# devices.net
KiCad netlist of a schematic drawn in Altium Designer
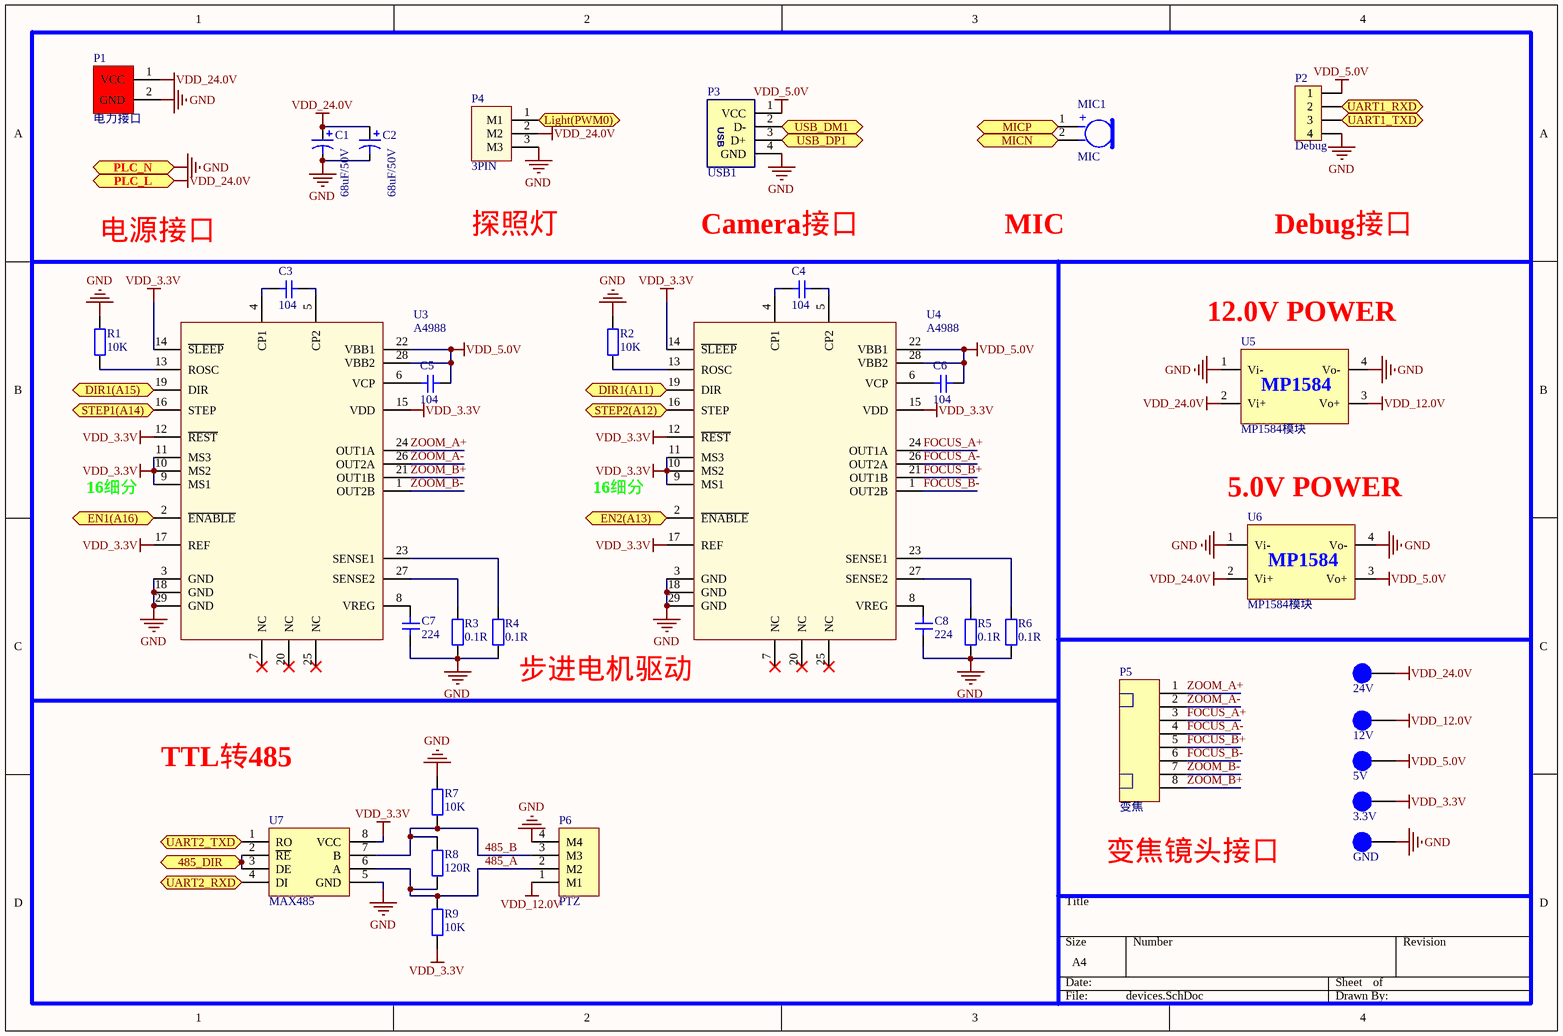
[diagram p0: devices.SchDoc]

(export (version "E")
  (design (tool "Eeschema 10.0.6"))
  (components
    (comp (ref "C1")
      (value "68uF/50V")
      (footprint "RB.1.2")
      (description "直插极性电容")
      (libsource (lib "集大电协1.5") (part "Cap3"))
    )
    (comp (ref "C2")
      (value "68uF/50V")
      (footprint "RB.1.2")
      (description "直插极性电容")
      (libsource (lib "集大电协1.5") (part "Cap3"))
    )
    (comp (ref "C3")
      (value "104")
      (footprint "0603C")
      (description "无极贴片电容")
      (libsource (lib "集大电协1.5") (part "Cap1"))
    )
    (comp (ref "C4")
      (value "104")
      (footprint "0603C")
      (description "无极贴片电容")
      (libsource (lib "集大电协1.5") (part "Cap1"))
    )
    (comp (ref "C5")
      (value "104")
      (footprint "0603C")
      (description "无极贴片电容")
      (libsource (lib "集大电协1.5") (part "Cap1"))
    )
    (comp (ref "C6")
      (value "104")
      (footprint "0603C")
      (description "无极贴片电容")
      (libsource (lib "集大电协1.5") (part "Cap1"))
    )
    (comp (ref "C7")
      (value "224")
      (footprint "0603C")
      (description "无极贴片电容")
      (libsource (lib "集大电协1.5") (part "Cap1"))
    )
    (comp (ref "C8")
      (value "224")
      (footprint "0603C")
      (description "无极贴片电容")
      (libsource (lib "集大电协1.5") (part "Cap1"))
    )
    (comp (ref "MIC1") (value "MIC") (footprint "MIC") (libsource (lib "集大电协1.5") (part "MIC")))
    (comp (ref "P1") (value "电力接口") (footprint "PH2.0WS-2P") (libsource (lib "集大电协1.5") (part "电源端子")))
    (comp (ref "P2")
      (value "Debug")
      (footprint "MX1.25WS-4PIN")
      (description "排针")
      (libsource (lib "集大电协1.5") (part "Header 4"))
    )
    (comp (ref "P3") (value "USB1") (footprint "PH2.0WS-4P") (libsource (lib "集大电协1.5") (part "USB")))
    (comp (ref "P4") (value "3PIN") (footprint "PH2.0WS-3P") (libsource (lib "集大电协1.5") (part "接线端子-3PIN")))
    (comp (ref "P5") (value "变焦") (footprint "MX1.25WS-8P") (libsource (lib "集大电协1.5") (part "接线端子-8PIN")))
    (comp (ref "P6")
      (value "PTZ")
      (footprint "PH2.0WS-4P")
      (description "4PIN")
      (libsource (lib "集大电协1.5") (part "接线端子-4PIN"))
    )
    (comp (ref "R1")
      (value "10K")
      (footprint "0603R")
      (description "电阻")
      (libsource (lib "集大电协1.5") (part "Res"))
    )
    (comp (ref "R2")
      (value "10K")
      (footprint "0603R")
      (description "电阻")
      (libsource (lib "集大电协1.5") (part "Res"))
    )
    (comp (ref "R3")
      (value "0.1R")
      (footprint "0805R")
      (description "电阻")
      (libsource (lib "集大电协1.5") (part "Res"))
    )
    (comp (ref "R4")
      (value "0.1R")
      (footprint "0805R")
      (description "电阻")
      (libsource (lib "集大电协1.5") (part "Res"))
    )
    (comp (ref "R5")
      (value "0.1R")
      (footprint "0805R")
      (description "电阻")
      (libsource (lib "集大电协1.5") (part "Res"))
    )
    (comp (ref "R6")
      (value "0.1R")
      (footprint "0805R")
      (description "电阻")
      (libsource (lib "集大电协1.5") (part "Res"))
    )
    (comp (ref "R7")
      (value "10K")
      (footprint "0603R")
      (description "电阻")
      (libsource (lib "集大电协1.5") (part "Res"))
    )
    (comp (ref "R8")
      (value "120R")
      (footprint "0603R")
      (description "电阻")
      (libsource (lib "集大电协1.5") (part "Res"))
    )
    (comp (ref "R9")
      (value "10K")
      (footprint "0603R")
      (description "电阻")
      (libsource (lib "集大电协1.5") (part "Res"))
    )
    (comp (ref "T1")
      (value "24V")
      (footprint "PIN 1(贴片)")
      (description "测试点")
      (libsource (lib "集大电协1.2") (part "测试点"))
    )
    (comp (ref "T2")
      (value "12V")
      (footprint "PIN 1(贴片)")
      (description "测试点")
      (libsource (lib "集大电协1.2") (part "测试点"))
    )
    (comp (ref "T3")
      (value "5V")
      (footprint "PIN 1(贴片)")
      (description "测试点")
      (libsource (lib "集大电协1.2") (part "测试点"))
    )
    (comp (ref "T4")
      (value "3.3V")
      (footprint "PIN 1(贴片)")
      (description "测试点")
      (libsource (lib "集大电协1.2") (part "测试点"))
    )
    (comp (ref "T5")
      (value "GND")
      (footprint "PIN 1(贴片)")
      (description "测试点")
      (libsource (lib "集大电协1.2") (part "测试点"))
    )
    (comp (ref "U3") (value "A4988") (footprint "QFN-28") (libsource (lib "集大电协1.5") (part "A4988")))
    (comp (ref "U4") (value "A4988") (footprint "QFN-28") (libsource (lib "集大电协1.5") (part "A4988")))
    (comp (ref "U5")
      (value "MP1584模块")
      (footprint "MP1584电源模块")
      (libsource (lib "集大电协1.5") (part "MP1584电源模块"))
    )
    (comp (ref "U6")
      (value "MP1584模块")
      (footprint "MP1584电源模块")
      (libsource (lib "集大电协1.5") (part "MP1584电源模块"))
    )
    (comp (ref "U7") (value "MAX485") (footprint "SOP-8") (libsource (lib "集大电协1.5") (part "MAX485")))
  )
  (nets
    (net (code "1") (name "/485_A") (class "Default")
      (node (ref "P6") (pin "2") (pinfunction "M2_2") (pintype "passive"))
      (node (ref "R8") (pin "1") (pinfunction "1_1") (pintype "passive"))
      (node (ref "R9") (pin "2") (pinfunction "2_2") (pintype "passive"))
      (node (ref "U7") (pin "6") (pinfunction "A_6") (pintype "passive"))
    )
    (net (code "2") (name "/485_B") (class "Default")
      (node (ref "P6") (pin "3") (pinfunction "M3_3") (pintype "passive"))
      (node (ref "R7") (pin "1") (pinfunction "1_1") (pintype "passive"))
      (node (ref "R8") (pin "2") (pinfunction "2_2") (pintype "passive"))
      (node (ref "U7") (pin "7") (pinfunction "B_7") (pintype "passive"))
    )
    (net (code "3") (name "/485_DIR") (class "Default")
      (node (ref "U7") (pin "2") (pinfunction "~{RE}_2") (pintype "passive"))
      (node (ref "U7") (pin "3") (pinfunction "DE_3") (pintype "passive"))
    )
    (net (code "4") (name "/DIR1(A11)") (class "Default")
      (node (ref "U4") (pin "19") (pinfunction "DIR_19") (pintype "passive"))
    )
    (net (code "5") (name "/DIR1(A15)") (class "Default")
      (node (ref "U3") (pin "19") (pinfunction "DIR_19") (pintype "passive"))
    )
    (net (code "6") (name "/EN1(A16)") (class "Default")
      (node (ref "U3") (pin "2") (pinfunction "~{ENABLE}_2") (pintype "passive"))
    )
    (net (code "7") (name "/EN2(A13)") (class "Default")
      (node (ref "U4") (pin "2") (pinfunction "~{ENABLE}_2") (pintype "passive"))
    )
    (net (code "8") (name "/FOCUS_A+") (class "Default")
      (node (ref "P5") (pin "3") (pinfunction "3_3") (pintype "passive"))
      (node (ref "U4") (pin "24") (pinfunction "OUT1A_24") (pintype "passive"))
    )
    (net (code "9") (name "/FOCUS_A-") (class "Default")
      (node (ref "P5") (pin "4") (pinfunction "4_4") (pintype "passive"))
      (node (ref "U4") (pin "26") (pinfunction "OUT2A_26") (pintype "passive"))
    )
    (net (code "10") (name "/FOCUS_B+") (class "Default")
      (node (ref "P5") (pin "5") (pinfunction "5_5") (pintype "passive"))
      (node (ref "U4") (pin "21") (pinfunction "OUT1B_21") (pintype "passive"))
    )
    (net (code "11") (name "/FOCUS_B-") (class "Default")
      (node (ref "P5") (pin "6") (pinfunction "6_6") (pintype "passive"))
      (node (ref "U4") (pin "1") (pinfunction "OUT2B_1") (pintype "passive"))
    )
    (net (code "12") (name "/Light(PWM0)") (class "Default")
      (node (ref "P4") (pin "1") (pinfunction "M1_1") (pintype "passive"))
    )
    (net (code "13") (name "/MICN") (class "Default")
      (node (ref "MIC1") (pin "2") (pinfunction "N_2") (pintype "passive"))
    )
    (net (code "14") (name "/MICP") (class "Default")
      (node (ref "MIC1") (pin "1") (pinfunction "P_1") (pintype "passive"))
    )
    (net (code "15") (name "/STEP1(A14)") (class "Default")
      (node (ref "U3") (pin "16") (pinfunction "STEP_16") (pintype "passive"))
    )
    (net (code "16") (name "/STEP2(A12)") (class "Default")
      (node (ref "U4") (pin "16") (pinfunction "STEP_16") (pintype "passive"))
    )
    (net (code "17") (name "/UART1_RXD") (class "Default")
      (node (ref "P2") (pin "2") (pinfunction "2_2") (pintype "passive"))
    )
    (net (code "18") (name "/UART1_TXD") (class "Default")
      (node (ref "P2") (pin "3") (pinfunction "3_3") (pintype "passive"))
    )
    (net (code "19") (name "/UART2_RXD") (class "Default")
      (node (ref "U7") (pin "4") (pinfunction "DI_4") (pintype "passive"))
    )
    (net (code "20") (name "/UART2_TXD") (class "Default")
      (node (ref "U7") (pin "1") (pinfunction "RO_1") (pintype "passive"))
    )
    (net (code "21") (name "/USB_DM1") (class "Default")
      (node (ref "P3") (pin "2") (pinfunction "D-_2") (pintype "passive"))
    )
    (net (code "22") (name "/USB_DP1") (class "Default")
      (node (ref "P3") (pin "3") (pinfunction "D+_3") (pintype "passive"))
    )
    (net (code "23") (name "/ZOOM_A+") (class "Default")
      (node (ref "P5") (pin "1") (pinfunction "1_1") (pintype "passive"))
      (node (ref "U3") (pin "24") (pinfunction "OUT1A_24") (pintype "passive"))
    )
    (net (code "24") (name "/ZOOM_A-") (class "Default")
      (node (ref "P5") (pin "2") (pinfunction "2_2") (pintype "passive"))
      (node (ref "U3") (pin "26") (pinfunction "OUT2A_26") (pintype "passive"))
    )
    (net (code "25") (name "/ZOOM_B+") (class "Default")
      (node (ref "P5") (pin "8") (pinfunction "8_8") (pintype "passive"))
      (node (ref "U3") (pin "21") (pinfunction "OUT1B_21") (pintype "passive"))
    )
    (net (code "26") (name "/ZOOM_B-") (class "Default")
      (node (ref "P5") (pin "7") (pinfunction "7_7") (pintype "passive"))
      (node (ref "U3") (pin "1") (pinfunction "OUT2B_1") (pintype "passive"))
    )
    (net (code "27") (name "GND") (class "Default")
      (node (ref "C1") (pin "2") (pinfunction "2_2") (pintype "passive"))
      (node (ref "C2") (pin "2") (pinfunction "2_2") (pintype "passive"))
      (node (ref "C7") (pin "1") (pinfunction "1_1") (pintype "passive"))
      (node (ref "C8") (pin "1") (pinfunction "1_1") (pintype "passive"))
      (node (ref "P1") (pin "2") (pinfunction "GND_2") (pintype "passive"))
      (node (ref "P2") (pin "4") (pinfunction "4_4") (pintype "passive"))
      (node (ref "P3") (pin "4") (pinfunction "GND_4") (pintype "passive"))
      (node (ref "P4") (pin "3") (pinfunction "M3_3") (pintype "passive"))
      (node (ref "P6") (pin "4") (pinfunction "M4_4") (pintype "passive"))
      (node (ref "R1") (pin "1") (pinfunction "1_1") (pintype "passive"))
      (node (ref "R2") (pin "1") (pinfunction "1_1") (pintype "passive"))
      (node (ref "R3") (pin "1") (pinfunction "1_1") (pintype "passive"))
      (node (ref "R4") (pin "1") (pinfunction "1_1") (pintype "passive"))
      (node (ref "R5") (pin "1") (pinfunction "1_1") (pintype "passive"))
      (node (ref "R6") (pin "1") (pinfunction "1_1") (pintype "passive"))
      (node (ref "R7") (pin "2") (pinfunction "2_2") (pintype "passive"))
      (node (ref "T5") (pin "1") (pinfunction "1_1") (pintype "passive"))
      (node (ref "U3") (pin "18") (pinfunction "GND_18") (pintype "passive"))
      (node (ref "U3") (pin "29") (pinfunction "GND_29") (pintype "passive"))
      (node (ref "U3") (pin "3") (pinfunction "GND_3") (pintype "passive"))
      (node (ref "U4") (pin "18") (pinfunction "GND_18") (pintype "passive"))
      (node (ref "U4") (pin "29") (pinfunction "GND_29") (pintype "passive"))
      (node (ref "U4") (pin "3") (pinfunction "GND_3") (pintype "passive"))
      (node (ref "U5") (pin "1") (pinfunction "Vi-_1") (pintype "passive"))
      (node (ref "U5") (pin "4") (pinfunction "Vo-_4") (pintype "passive"))
      (node (ref "U6") (pin "1") (pinfunction "Vi-_1") (pintype "passive"))
      (node (ref "U6") (pin "4") (pinfunction "Vo-_4") (pintype "passive"))
      (node (ref "U7") (pin "5") (pinfunction "GND_5") (pintype "passive"))
    )
    (net (code "28") (name "Net-(U3-CP1)") (class "Default")
      (node (ref "C3") (pin "1") (pinfunction "1_1") (pintype "passive"))
      (node (ref "U3") (pin "4") (pinfunction "CP1_4") (pintype "passive"))
    )
    (net (code "29") (name "Net-(U3-CP2)") (class "Default")
      (node (ref "C3") (pin "2") (pinfunction "2_2") (pintype "passive"))
      (node (ref "U3") (pin "5") (pinfunction "CP2_5") (pintype "passive"))
    )
    (net (code "30") (name "Net-(U3-ROSC)") (class "Default")
      (node (ref "R1") (pin "2") (pinfunction "2_2") (pintype "passive"))
      (node (ref "U3") (pin "13") (pinfunction "ROSC_13") (pintype "passive"))
    )
    (net (code "31") (name "Net-(U3-SENSE1)") (class "Default")
      (node (ref "R4") (pin "2") (pinfunction "2_2") (pintype "passive"))
      (node (ref "U3") (pin "23") (pinfunction "SENSE1_23") (pintype "passive"))
    )
    (net (code "32") (name "Net-(U3-SENSE2)") (class "Default")
      (node (ref "R3") (pin "2") (pinfunction "2_2") (pintype "passive"))
      (node (ref "U3") (pin "27") (pinfunction "SENSE2_27") (pintype "passive"))
    )
    (net (code "33") (name "Net-(U3-VCP)") (class "Default")
      (node (ref "C5") (pin "1") (pinfunction "1_1") (pintype "passive"))
      (node (ref "U3") (pin "6") (pinfunction "VCP_6") (pintype "passive"))
    )
    (net (code "34") (name "Net-(U3-VREG)") (class "Default")
      (node (ref "C7") (pin "2") (pinfunction "2_2") (pintype "passive"))
      (node (ref "U3") (pin "8") (pinfunction "VREG_8") (pintype "passive"))
    )
    (net (code "35") (name "Net-(U4-CP1)") (class "Default")
      (node (ref "C4") (pin "1") (pinfunction "1_1") (pintype "passive"))
      (node (ref "U4") (pin "4") (pinfunction "CP1_4") (pintype "passive"))
    )
    (net (code "36") (name "Net-(U4-CP2)") (class "Default")
      (node (ref "C4") (pin "2") (pinfunction "2_2") (pintype "passive"))
      (node (ref "U4") (pin "5") (pinfunction "CP2_5") (pintype "passive"))
    )
    (net (code "37") (name "Net-(U4-ROSC)") (class "Default")
      (node (ref "R2") (pin "2") (pinfunction "2_2") (pintype "passive"))
      (node (ref "U4") (pin "13") (pinfunction "ROSC_13") (pintype "passive"))
    )
    (net (code "38") (name "Net-(U4-SENSE1)") (class "Default")
      (node (ref "R6") (pin "2") (pinfunction "2_2") (pintype "passive"))
      (node (ref "U4") (pin "23") (pinfunction "SENSE1_23") (pintype "passive"))
    )
    (net (code "39") (name "Net-(U4-SENSE2)") (class "Default")
      (node (ref "R5") (pin "2") (pinfunction "2_2") (pintype "passive"))
      (node (ref "U4") (pin "27") (pinfunction "SENSE2_27") (pintype "passive"))
    )
    (net (code "40") (name "Net-(U4-VCP)") (class "Default")
      (node (ref "C6") (pin "1") (pinfunction "1_1") (pintype "passive"))
      (node (ref "U4") (pin "6") (pinfunction "VCP_6") (pintype "passive"))
    )
    (net (code "41") (name "Net-(U4-VREG)") (class "Default")
      (node (ref "C8") (pin "2") (pinfunction "2_2") (pintype "passive"))
      (node (ref "U4") (pin "8") (pinfunction "VREG_8") (pintype "passive"))
    )
    (net (code "42") (name "VDD_3.3V") (class "Default")
      (node (ref "R9") (pin "1") (pinfunction "1_1") (pintype "passive"))
      (node (ref "T4") (pin "1") (pinfunction "1_1") (pintype "passive"))
      (node (ref "U3") (pin "10") (pinfunction "MS2_10") (pintype "passive"))
      (node (ref "U3") (pin "11") (pinfunction "MS3_11") (pintype "passive"))
      (node (ref "U3") (pin "12") (pinfunction "~{REST}_12") (pintype "passive"))
      (node (ref "U3") (pin "14") (pinfunction "~{SLEEP}_14") (pintype "passive"))
      (node (ref "U3") (pin "15") (pinfunction "VDD_15") (pintype "passive"))
      (node (ref "U3") (pin "17") (pinfunction "REF_17") (pintype "passive"))
      (node (ref "U3") (pin "9") (pinfunction "MS1_9") (pintype "passive"))
      (node (ref "U4") (pin "10") (pinfunction "MS2_10") (pintype "passive"))
      (node (ref "U4") (pin "11") (pinfunction "MS3_11") (pintype "passive"))
      (node (ref "U4") (pin "12") (pinfunction "~{REST}_12") (pintype "passive"))
      (node (ref "U4") (pin "14") (pinfunction "~{SLEEP}_14") (pintype "passive"))
      (node (ref "U4") (pin "15") (pinfunction "VDD_15") (pintype "passive"))
      (node (ref "U4") (pin "17") (pinfunction "REF_17") (pintype "passive"))
      (node (ref "U4") (pin "9") (pinfunction "MS1_9") (pintype "passive"))
      (node (ref "U7") (pin "8") (pinfunction "VCC_8") (pintype "passive"))
    )
    (net (code "43") (name "VDD_5.0V") (class "Default")
      (node (ref "C5") (pin "2") (pinfunction "2_2") (pintype "passive"))
      (node (ref "C6") (pin "2") (pinfunction "2_2") (pintype "passive"))
      (node (ref "P2") (pin "1") (pinfunction "1_1") (pintype "passive"))
      (node (ref "P3") (pin "1") (pinfunction "VCC_1") (pintype "passive"))
      (node (ref "T3") (pin "1") (pinfunction "1_1") (pintype "passive"))
      (node (ref "U3") (pin "22") (pinfunction "VBB1_22") (pintype "passive"))
      (node (ref "U3") (pin "28") (pinfunction "VBB2_28") (pintype "passive"))
      (node (ref "U4") (pin "22") (pinfunction "VBB1_22") (pintype "passive"))
      (node (ref "U4") (pin "28") (pinfunction "VBB2_28") (pintype "passive"))
      (node (ref "U6") (pin "3") (pinfunction "Vo+_3") (pintype "passive"))
    )
    (net (code "44") (name "VDD_12.0V") (class "Default")
      (node (ref "P6") (pin "1") (pinfunction "M1_1") (pintype "passive"))
      (node (ref "T2") (pin "1") (pinfunction "1_1") (pintype "passive"))
      (node (ref "U5") (pin "3") (pinfunction "Vo+_3") (pintype "passive"))
    )
    (net (code "45") (name "VDD_24.0V") (class "Default")
      (node (ref "C1") (pin "1") (pinfunction "1_1") (pintype "passive"))
      (node (ref "C2") (pin "1") (pinfunction "1_1") (pintype "passive"))
      (node (ref "P1") (pin "1") (pinfunction "VCC_1") (pintype "passive"))
      (node (ref "P4") (pin "2") (pinfunction "M2_2") (pintype "passive"))
      (node (ref "T1") (pin "1") (pinfunction "1_1") (pintype "passive"))
      (node (ref "U5") (pin "2") (pinfunction "Vi+_2") (pintype "passive"))
      (node (ref "U6") (pin "2") (pinfunction "Vi+_2") (pintype "passive"))
    )
    (net (code "46") (name "unconnected-(U3-NC-Pad7)") (class "Default")
      (node (ref "U3") (pin "7") (pinfunction "NC_7") (pintype "passive+no_connect"))
    )
    (net (code "47") (name "unconnected-(U3-NC-Pad20)") (class "Default")
      (node (ref "U3") (pin "20") (pinfunction "NC_20") (pintype "passive+no_connect"))
    )
    (net (code "48") (name "unconnected-(U3-NC-Pad25)") (class "Default")
      (node (ref "U3") (pin "25") (pinfunction "NC_25") (pintype "passive+no_connect"))
    )
    (net (code "49") (name "unconnected-(U4-NC-Pad7)") (class "Default")
      (node (ref "U4") (pin "7") (pinfunction "NC_7") (pintype "passive+no_connect"))
    )
    (net (code "50") (name "unconnected-(U4-NC-Pad20)") (class "Default")
      (node (ref "U4") (pin "20") (pinfunction "NC_20") (pintype "passive+no_connect"))
    )
    (net (code "51") (name "unconnected-(U4-NC-Pad25)") (class "Default")
      (node (ref "U4") (pin "25") (pinfunction "NC_25") (pintype "passive+no_connect"))
    )
  )
)
